# match4.net
KiCad netlist of a schematic drawn in EAGLE
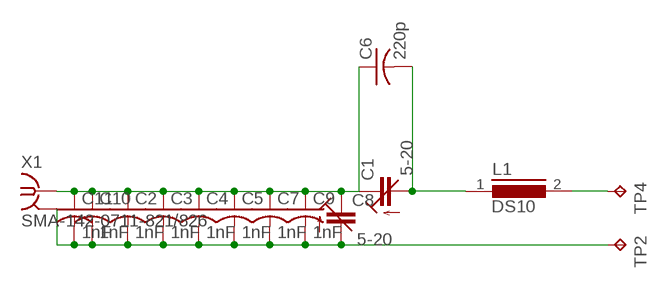
[diagram p0: schematic, sheet 1]

(export (version "E")
  (design (tool "Eeschema 10.0.6"))
  (components
    (comp (ref "C1")
      (value "5-20")
      (footprint "eagle-import:SGC3S")
      (libsource (lib "eagle-import") (part "C-TRIMM"))
    )
    (comp (ref "C2")
      (value "1nF")
      (footprint "eagle-import:1111")
      (libsource (lib "eagle-import") (part "C-US"))
    )
    (comp (ref "C3")
      (value "1nF")
      (footprint "eagle-import:1111")
      (libsource (lib "eagle-import") (part "C-US"))
    )
    (comp (ref "C4")
      (value "1nF")
      (footprint "eagle-import:1111")
      (libsource (lib "eagle-import") (part "C-US"))
    )
    (comp (ref "C5")
      (value "1nF")
      (footprint "eagle-import:1111")
      (libsource (lib "eagle-import") (part "C-US"))
    )
    (comp (ref "C6")
      (value "220p")
      (footprint "eagle-import:1111")
      (libsource (lib "eagle-import") (part "C-US"))
    )
    (comp (ref "C7")
      (value "1nF")
      (footprint "eagle-import:1111")
      (libsource (lib "eagle-import") (part "C-US"))
    )
    (comp (ref "C8")
      (value "5-20")
      (footprint "eagle-import:SGC3S")
      (libsource (lib "eagle-import") (part "C-TRIMM"))
    )
    (comp (ref "C9")
      (value "1nF")
      (footprint "eagle-import:1111")
      (libsource (lib "eagle-import") (part "C-US"))
    )
    (comp (ref "C10")
      (value "1nF")
      (footprint "eagle-import:1111")
      (libsource (lib "eagle-import") (part "C-US"))
    )
    (comp (ref "C11")
      (value "1nF")
      (footprint "eagle-import:1111")
      (libsource (lib "eagle-import") (part "C-US"))
    )
    (comp (ref "L1")
      (value "DS10")
      (footprint "eagle-import:DS10")
      (libsource (lib "eagle-import") (part "DS10"))
    )
    (comp (ref "TP2")
      (value "TPPAD1-13Y")
      (footprint "eagle-import:P1-13Y")
      (libsource (lib "eagle-import") (part "TPPAD1-13Y"))
    )
    (comp (ref "TP4")
      (value "TPPAD1-13Y")
      (footprint "eagle-import:P1-13Y")
      (libsource (lib "eagle-import") (part "TPPAD1-13Y"))
    )
    (comp (ref "X1")
      (value "SMA-142-0711-821/826")
      (footprint "eagle-import:J502-ND-142-0711-821_826")
      (fields (field (name "MF") "JOHNSON COMPONENTS") (field (name "MPN") "142-0711-821"))
      (libsource (lib "eagle-import") (part "SMA-142-0711-821/826"))
    )
  )
  (nets
    (net (code "1") (name "Net-(C1-A)") (class "Default")
      (node (ref "C1") (pin "P$1") (pinfunction "A_P$1") (pintype "passive"))
      (node (ref "C6") (pin "P$2") (pinfunction "2_P$2") (pintype "passive"))
      (node (ref "L1") (pin "1") (pinfunction "1_1") (pintype "passive"))
    )
    (net (code "2") (name "Net-(C1-E)") (class "Default")
      (node (ref "C1") (pin "P$2") (pinfunction "E_P$2") (pintype "passive"))
      (node (ref "C10") (pin "P$1") (pinfunction "1_P$1") (pintype "passive"))
      (node (ref "C11") (pin "P$1") (pinfunction "1_P$1") (pintype "passive"))
      (node (ref "C2") (pin "P$1") (pinfunction "1_P$1") (pintype "passive"))
      (node (ref "C3") (pin "P$1") (pinfunction "1_P$1") (pintype "passive"))
      (node (ref "C4") (pin "P$1") (pinfunction "1_P$1") (pintype "passive"))
      (node (ref "C5") (pin "P$1") (pinfunction "1_P$1") (pintype "passive"))
      (node (ref "C6") (pin "P$1") (pinfunction "1_P$1") (pintype "passive"))
      (node (ref "C7") (pin "P$1") (pinfunction "1_P$1") (pintype "passive"))
      (node (ref "C8") (pin "P$2") (pinfunction "E_P$2") (pintype "passive"))
      (node (ref "C9") (pin "P$1") (pinfunction "1_P$1") (pintype "passive"))
      (node (ref "X1") (pin "1") (pinfunction "1_1") (pintype "passive"))
    )
    (net (code "3") (name "Net-(C10-2)") (class "Default")
      (node (ref "C10") (pin "P$2") (pinfunction "2_P$2") (pintype "passive"))
      (node (ref "C11") (pin "P$2") (pinfunction "2_P$2") (pintype "passive"))
      (node (ref "C2") (pin "P$2") (pinfunction "2_P$2") (pintype "passive"))
      (node (ref "C3") (pin "P$2") (pinfunction "2_P$2") (pintype "passive"))
      (node (ref "C4") (pin "P$2") (pinfunction "2_P$2") (pintype "passive"))
      (node (ref "C5") (pin "P$2") (pinfunction "2_P$2") (pintype "passive"))
      (node (ref "C7") (pin "P$2") (pinfunction "2_P$2") (pintype "passive"))
      (node (ref "C8") (pin "P$1") (pinfunction "A_P$1") (pintype "passive"))
      (node (ref "C9") (pin "P$2") (pinfunction "2_P$2") (pintype "passive"))
      (node (ref "TP2") (pin "TP") (pinfunction "TP_TP") (pintype "input"))
      (node (ref "X1") (pin "G@1") (pinfunction "2_G@1") (pintype "passive"))
      (node (ref "X1") (pin "G@2") (pinfunction "2_G@2") (pintype "passive"))
      (node (ref "X1") (pin "G@3") (pinfunction "2_G@3") (pintype "passive"))
      (node (ref "X1") (pin "G@4") (pinfunction "2_G@4") (pintype "passive"))
    )
    (net (code "4") (name "Net-(L1-Pad2)") (class "Default")
      (node (ref "L1") (pin "2") (pinfunction "2_2") (pintype "passive"))
      (node (ref "TP4") (pin "TP") (pinfunction "TP_TP") (pintype "input"))
    )
  )
)
